# CAN-UART.net
KiCad netlist of a schematic drawn in Altium Designer
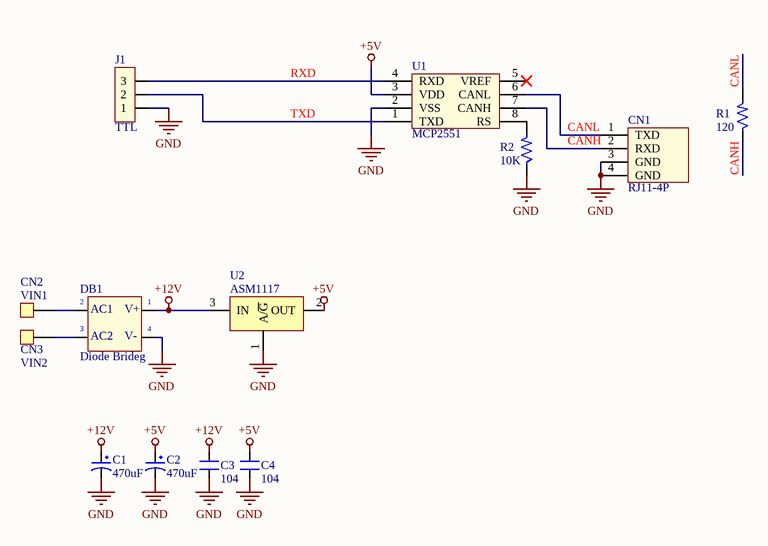
[diagram p0: CAN-UART.SchDoc]

(export (version "E")
  (design (tool "Eeschema 10.0.6"))
  (components
    (comp (ref "C1")
      (value "470uF")
      (footprint "C-ALU-D6.5")
      (description "Cap P  0,1uF < 22uF , 16 - 50V")
      (libsource (lib "PART") (part "CP1"))
    )
    (comp (ref "C2")
      (value "470uF")
      (footprint "C-ALU-D6.5")
      (description "Cap P  0,1uF < 22uF , 16 - 50V")
      (libsource (lib "PART") (part "CP1"))
    )
    (comp (ref "C3")
      (value "104")
      (footprint "C-0805")
      (fields (field (name "DESIGNED BY") "VanDungEvn"))
      (libsource (lib "syhaunguyen") (part "CN"))
    )
    (comp (ref "C4")
      (value "104")
      (footprint "C-0805")
      (fields (field (name "DESIGNED BY") "VanDungEvn"))
      (libsource (lib "syhaunguyen") (part "CN"))
    )
    (comp (ref "CN1") (value "RJ11-4P") (libsource (lib "doAnTotNghiep2017Lib") (part "RJ11-4P")))
    (comp (ref "CN2")
      (value "VIN1")
      (footprint "M3")
      (libsource (lib "doAnTotNghiep2017Lib") (part "COCDONGM3"))
    )
    (comp (ref "CN3")
      (value "VIN2")
      (footprint "M3")
      (libsource (lib "doAnTotNghiep2017Lib") (part "COCDONGM3"))
    )
    (comp (ref "DB1")
      (value "Diode Brideg")
      (footprint "D-DB-1A-SMD")
      (description "Convert AC to DC voltage, 4 pin")
      (libsource (lib "PART") (part "DB"))
    )
    (comp (ref "J1")
      (value "TTL")
      (footprint "JP3")
      (description "Jumper 3")
      (libsource (lib "syhaunguyen") (part "JP3"))
    )
    (comp (ref "R1")
      (value "120")
      (footprint "R-0805")
      (description "Resistor 1/4W")
      (libsource (lib "syhaunguyen") (part "R"))
    )
    (comp (ref "R2")
      (value "10K")
      (footprint "R-0805")
      (description "Resistor 1/4W")
      (libsource (lib "syhaunguyen") (part "R"))
    )
    (comp (ref "U1")
      (value "MCP2551")
      (footprint "SOIC-8")
      (libsource (lib "doAnTotNghiep2017Lib") (part "MCP2551"))
    )
    (comp (ref "U2")
      (value "ASM1117")
      (footprint "TO-252")
      (libsource (lib "doAnTotNghiep2017Lib") (part "ASM1117"))
    )
  )
  (nets
    (net (code "1") (name "+5V") (class "Default")
      (node (ref "C2") (pin "1") (pinfunction "1_1") (pintype "passive"))
      (node (ref "C4") (pin "2") (pinfunction "2_2") (pintype "passive"))
      (node (ref "U1") (pin "3") (pinfunction "VDD_3") (pintype "passive"))
      (node (ref "U2") (pin "2") (pinfunction "OUT_2") (pintype "passive"))
    )
    (net (code "2") (name "+12V") (class "Default")
      (node (ref "C1") (pin "1") (pinfunction "1_1") (pintype "passive"))
      (node (ref "C3") (pin "2") (pinfunction "2_2") (pintype "passive"))
      (node (ref "DB1") (pin "3") (pinfunction "AC2_3") (pintype "passive"))
      (node (ref "U2") (pin "3") (pinfunction "IN_3") (pintype "passive"))
    )
    (net (code "3") (name "/CANH") (class "Default")
      (node (ref "CN1") (pin "2") (pinfunction "RXD_2") (pintype "passive"))
      (node (ref "R1") (pin "1") (pinfunction "1_1") (pintype "passive"))
      (node (ref "U1") (pin "7") (pinfunction "CANH_7") (pintype "passive"))
    )
    (net (code "4") (name "/CANL") (class "Default")
      (node (ref "CN1") (pin "1") (pinfunction "TXD_1") (pintype "passive"))
      (node (ref "R1") (pin "2") (pinfunction "2_2") (pintype "passive"))
      (node (ref "U1") (pin "6") (pinfunction "CANL_6") (pintype "passive"))
    )
    (net (code "5") (name "/RXD") (class "Default")
      (node (ref "J1") (pin "3") (pinfunction "3_3") (pintype "passive"))
      (node (ref "U1") (pin "4") (pinfunction "RXD_4") (pintype "passive"))
    )
    (net (code "6") (name "/TXD") (class "Default")
      (node (ref "J1") (pin "2") (pinfunction "2_2") (pintype "passive"))
      (node (ref "U1") (pin "1") (pinfunction "TXD_1") (pintype "passive"))
    )
    (net (code "7") (name "GND") (class "Default")
      (node (ref "C1") (pin "2") (pinfunction "2_2") (pintype "passive"))
      (node (ref "C2") (pin "2") (pinfunction "2_2") (pintype "passive"))
      (node (ref "C3") (pin "1") (pinfunction "1_1") (pintype "passive"))
      (node (ref "C4") (pin "1") (pinfunction "1_1") (pintype "passive"))
      (node (ref "CN1") (pin "3") (pinfunction "GND_3") (pintype "passive"))
      (node (ref "CN1") (pin "4") (pinfunction "GND_4") (pintype "passive"))
      (node (ref "DB1") (pin "4") (pinfunction "-V_OUT_4") (pintype "passive"))
      (node (ref "J1") (pin "1") (pinfunction "1_1") (pintype "passive"))
      (node (ref "R2") (pin "1") (pinfunction "1_1") (pintype "passive"))
      (node (ref "U1") (pin "2") (pinfunction "VSS_2") (pintype "passive"))
      (node (ref "U2") (pin "1") (pinfunction "A/~{G}_1") (pintype "passive"))
    )
    (net (code "8") (name "Net-(DB1-+V_OUT)") (class "Default")
      (node (ref "CN3") (pin "1") (pintype "passive"))
      (node (ref "DB1") (pin "1") (pinfunction "+V_OUT_1") (pintype "passive"))
    )
    (net (code "9") (name "Net-(DB1-AC1)") (class "Default")
      (node (ref "CN2") (pin "1") (pintype "passive"))
      (node (ref "DB1") (pin "2") (pinfunction "AC1_2") (pintype "passive"))
    )
    (net (code "10") (name "Net-(U1-RS)") (class "Default")
      (node (ref "R2") (pin "2") (pinfunction "2_2") (pintype "passive"))
      (node (ref "U1") (pin "8") (pinfunction "RS_8") (pintype "passive"))
    )
    (net (code "11") (name "unconnected-(U1-VREF-Pad5)") (class "Default")
      (node (ref "U1") (pin "5") (pinfunction "VREF_5") (pintype "passive+no_connect"))
    )
  )
)
